# ESP8266_Led_Driver.net
KiCad netlist of a schematic drawn in EAGLE
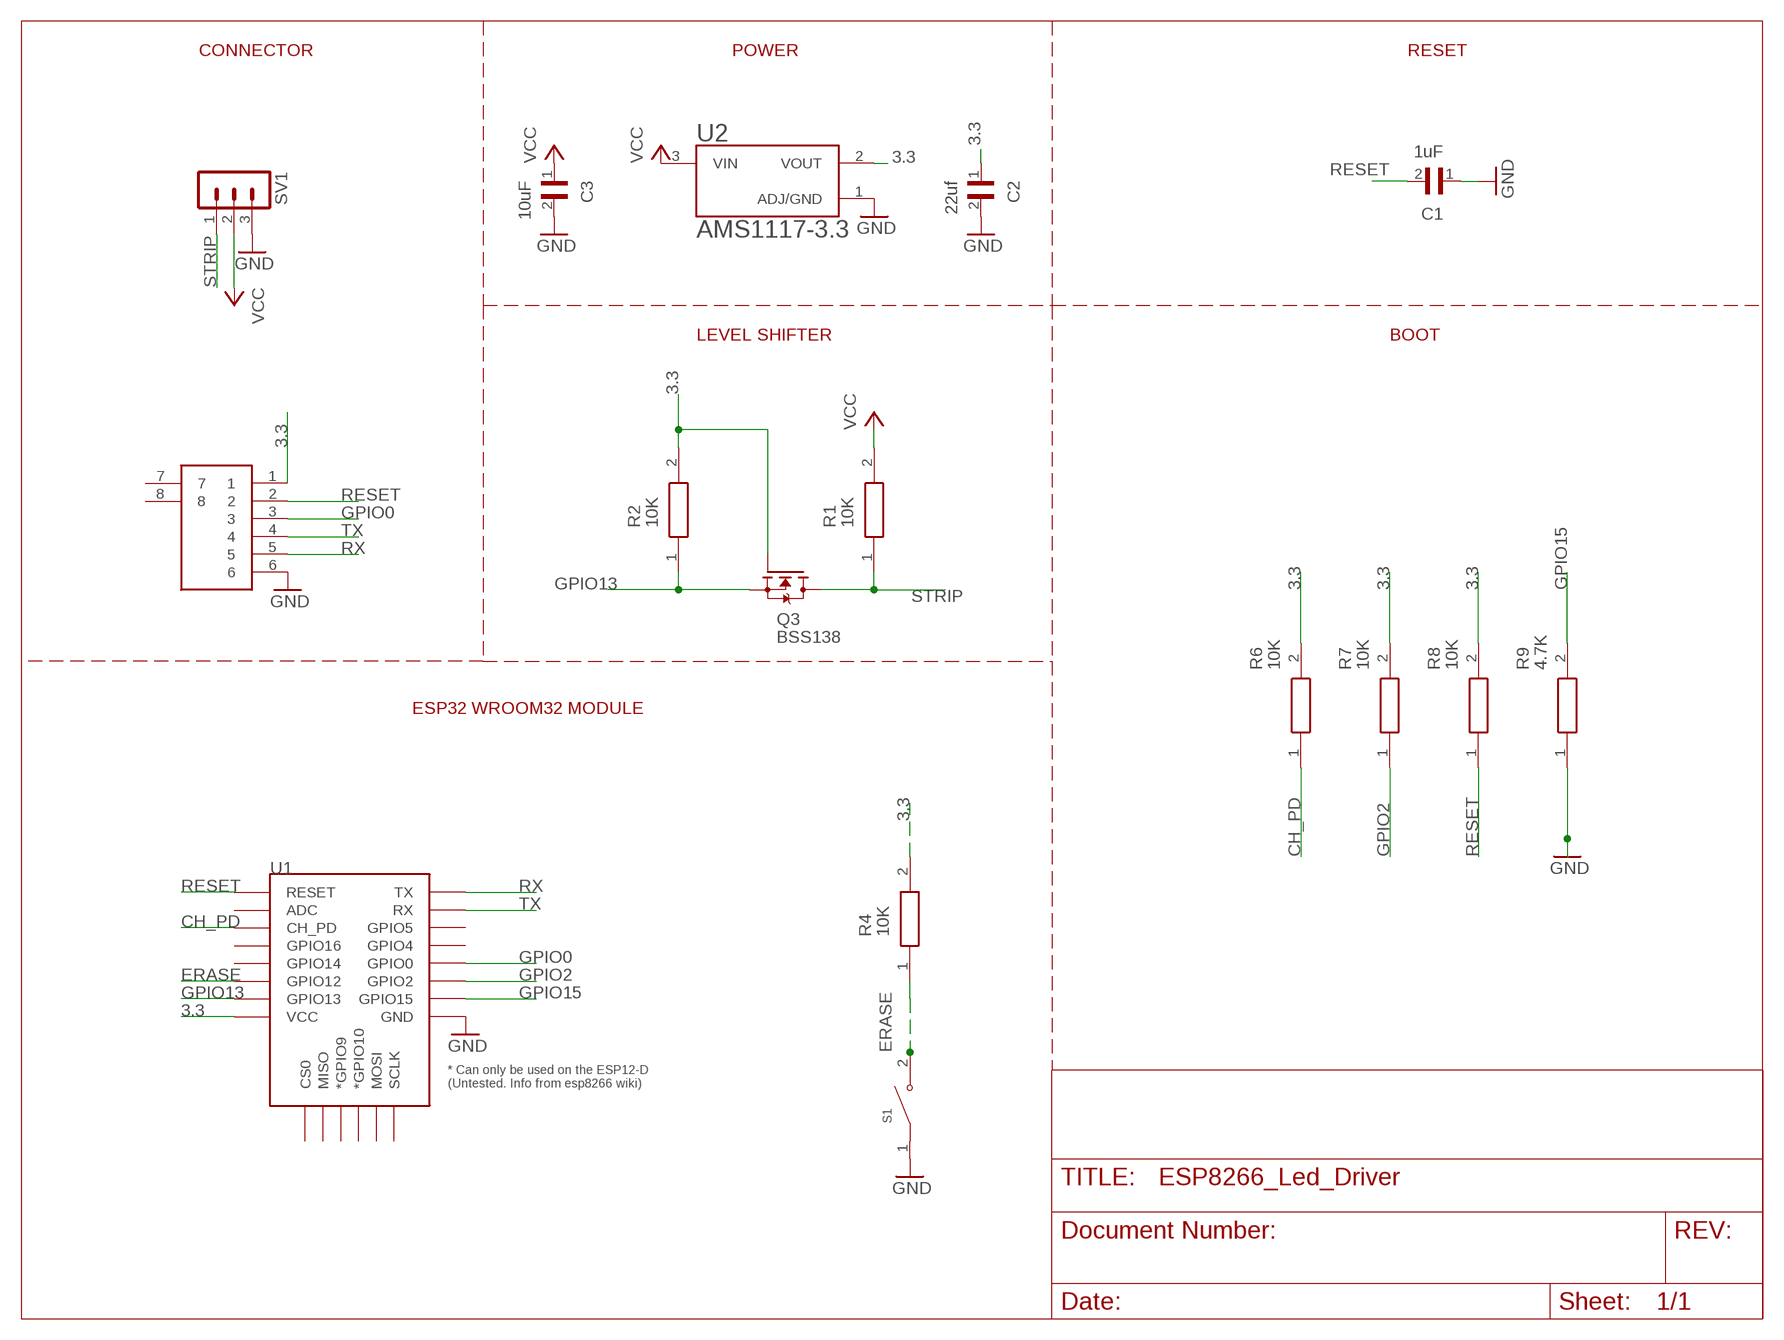
[diagram p0: schematic, sheet 1]

(export (version "E")
  (design (tool "Eeschema 10.0.6"))
  (components
    (comp (ref "C1")
      (value "1uF")
      (footprint "eagle-import:CAPC2012X94N")
      (fields (field (name "MF") "AVX") (field (name "MP") "0805YC103J4T2A"))
      (libsource (lib "eagle-import") (part "0805YC103J4T2A"))
    )
    (comp (ref "C2")
      (value "22uf")
      (footprint "eagle-import:CAPC2012X94N")
      (fields (field (name "MF") "AVX") (field (name "MP") "0805YC103J4T2A"))
      (libsource (lib "eagle-import") (part "0805YC103J4T2A"))
    )
    (comp (ref "C3")
      (value "10uF")
      (footprint "eagle-import:CAPC2012X94N")
      (fields (field (name "MF") "AVX") (field (name "MP") "0805YC103J4T2A"))
      (libsource (lib "eagle-import") (part "0805YC103J4T2A"))
    )
    (comp (ref "J1")
      (value "52852-0670")
      (footprint "eagle-import:528520670")
      (fields (field (name "MOUSER_PART_NUMBER") "538-52852-0670"))
      (libsource (lib "eagle-import") (part "52852-0670"))
    )
    (comp (ref "Q3")
      (value "BSS138")
      (footprint "eagle-import:SOT95P240X111-3N")
      (fields (field (name "MF") "ON Semiconductor"))
      (libsource (lib "eagle-import") (part "BSS138"))
    )
    (comp (ref "R1")
      (value "10K")
      (footprint "eagle-import:RESC1608X55N")
      (fields
        (field (name "MANUFACTURER_PART_NUMBER") "TNPW060330K0BXEA")
        (field (name "MOUSER_PART_NUMBER") "71-TNPW060330K0BXEA")
      )
      (libsource (lib "eagle-import") (part "TNPW060330K0BXEA"))
    )
    (comp (ref "R2")
      (value "10K")
      (footprint "eagle-import:RESC1608X55N")
      (fields
        (field (name "MANUFACTURER_PART_NUMBER") "TNPW060330K0BXEA")
        (field (name "MOUSER_PART_NUMBER") "71-TNPW060330K0BXEA")
      )
      (libsource (lib "eagle-import") (part "TNPW060330K0BXEA"))
    )
    (comp (ref "R4")
      (value "10K")
      (footprint "eagle-import:RESC1608X55N")
      (fields
        (field (name "MANUFACTURER_PART_NUMBER") "TNPW060330K0BXEA")
        (field (name "MOUSER_PART_NUMBER") "71-TNPW060330K0BXEA")
      )
      (libsource (lib "eagle-import") (part "TNPW060330K0BXEA"))
    )
    (comp (ref "R6")
      (value "10K")
      (footprint "eagle-import:RESC1608X55N")
      (fields
        (field (name "MANUFACTURER_PART_NUMBER") "TNPW060330K0BXEA")
        (field (name "MOUSER_PART_NUMBER") "71-TNPW060330K0BXEA")
      )
      (libsource (lib "eagle-import") (part "TNPW060330K0BXEA"))
    )
    (comp (ref "R7")
      (value "10K")
      (footprint "eagle-import:RESC1608X55N")
      (fields
        (field (name "MANUFACTURER_PART_NUMBER") "TNPW060330K0BXEA")
        (field (name "MOUSER_PART_NUMBER") "71-TNPW060330K0BXEA")
      )
      (libsource (lib "eagle-import") (part "TNPW060330K0BXEA"))
    )
    (comp (ref "R8")
      (value "10K")
      (footprint "eagle-import:RESC1608X55N")
      (fields
        (field (name "MANUFACTURER_PART_NUMBER") "TNPW060330K0BXEA")
        (field (name "MOUSER_PART_NUMBER") "71-TNPW060330K0BXEA")
      )
      (libsource (lib "eagle-import") (part "TNPW060330K0BXEA"))
    )
    (comp (ref "R9")
      (value "4.7K")
      (footprint "eagle-import:RESC1608X55N")
      (fields
        (field (name "MANUFACTURER_PART_NUMBER") "TNPW060330K0BXEA")
        (field (name "MOUSER_PART_NUMBER") "71-TNPW060330K0BXEA")
      )
      (libsource (lib "eagle-import") (part "TNPW060330K0BXEA"))
    )
    (comp (ref "S1")
      (value "PTS636_SM43J_SMTR_LFS")
      (footprint "eagle-import:SW_PTS636_SM43J_SMTR_LFS")
      (fields (field (name "MF") "C&K") (field (name "MP") "PTS636 SM43J SMTR LFS"))
      (libsource (lib "eagle-import") (part "PTS636_SM43J_SMTR_LFS"))
    )
    (comp (ref "SV1")
      (value "MA03-1")
      (footprint "eagle-import:MA03-1")
      (libsource (lib "eagle-import") (part "MA03-1"))
    )
    (comp (ref "U1")
      (value "ESP12ESMD")
      (footprint "eagle-import:ESP12E-SMD")
      (libsource (lib "eagle-import") (part "ESP12ESMD"))
    )
    (comp (ref "U2")
      (value "AMS1117-3.3")
      (footprint "eagle-import:SOT229P700X180-4N")
      (fields (field (name "MF") "Advanced Monolithic Systems"))
      (libsource (lib "eagle-import") (part "AMS1117-3.3"))
    )
  )
  (nets
    (net (code "1") (name "/3.3") (class "Default")
      (node (ref "C2") (pin "1") (pinfunction "1_1") (pintype "passive"))
      (node (ref "J1") (pin "1") (pinfunction "1_1") (pintype "bidirectional"))
      (node (ref "Q3") (pin "1") (pinfunction "G_1") (pintype "passive"))
      (node (ref "R2") (pin "2") (pinfunction "2_2") (pintype "bidirectional"))
      (node (ref "R4") (pin "2") (pinfunction "2_2") (pintype "bidirectional"))
      (node (ref "R6") (pin "2") (pinfunction "2_2") (pintype "bidirectional"))
      (node (ref "R7") (pin "2") (pinfunction "2_2") (pintype "bidirectional"))
      (node (ref "R8") (pin "2") (pinfunction "2_2") (pintype "bidirectional"))
      (node (ref "U1") (pin "VCC") (pinfunction "VCC_VCC") (pintype "bidirectional"))
      (node (ref "U2") (pin "2") (pinfunction "VOUT_2") (pintype "output"))
    )
    (net (code "2") (name "/CH_PD") (class "Default")
      (node (ref "R6") (pin "1") (pinfunction "1_1") (pintype "bidirectional"))
      (node (ref "U1") (pin "CH_PD") (pinfunction "CH_PD_CH_PD") (pintype "bidirectional"))
    )
    (net (code "3") (name "/ERASE") (class "Default")
      (node (ref "R4") (pin "1") (pinfunction "1_1") (pintype "bidirectional"))
      (node (ref "S1") (pin "2") (pinfunction "NO_2") (pintype "passive"))
      (node (ref "U1") (pin "GPIO12") (pinfunction "GPIO12_GPIO12") (pintype "bidirectional"))
    )
    (net (code "4") (name "/GPIO0") (class "Default")
      (node (ref "J1") (pin "3") (pinfunction "3_3") (pintype "bidirectional"))
      (node (ref "U1") (pin "GPIO0") (pinfunction "GPIO0_GPIO0") (pintype "bidirectional"))
    )
    (net (code "5") (name "/GPIO2") (class "Default")
      (node (ref "R7") (pin "1") (pinfunction "1_1") (pintype "bidirectional"))
      (node (ref "U1") (pin "GPIO2") (pinfunction "GPIO2_GPIO2") (pintype "bidirectional"))
    )
    (net (code "6") (name "/GPIO13") (class "Default")
      (node (ref "Q3") (pin "2") (pinfunction "S_2") (pintype "passive"))
      (node (ref "R2") (pin "1") (pinfunction "1_1") (pintype "bidirectional"))
      (node (ref "U1") (pin "GPIO13") (pinfunction "GPIO13_GPIO13") (pintype "bidirectional"))
    )
    (net (code "7") (name "/GPIO15") (class "Default")
      (node (ref "R9") (pin "2") (pinfunction "2_2") (pintype "bidirectional"))
      (node (ref "U1") (pin "GPIO15") (pinfunction "GPIO15_GPIO15") (pintype "bidirectional"))
    )
    (net (code "8") (name "/RESET") (class "Default")
      (node (ref "C1") (pin "2") (pinfunction "2_2") (pintype "passive"))
      (node (ref "J1") (pin "2") (pinfunction "2_2") (pintype "bidirectional"))
      (node (ref "R8") (pin "1") (pinfunction "1_1") (pintype "bidirectional"))
      (node (ref "U1") (pin "RESET") (pinfunction "RESET_RESET") (pintype "bidirectional"))
    )
    (net (code "9") (name "/RX") (class "Default")
      (node (ref "J1") (pin "5") (pinfunction "5_5") (pintype "bidirectional"))
      (node (ref "U1") (pin "TXD0") (pinfunction "TX_TXD0") (pintype "bidirectional"))
    )
    (net (code "10") (name "/STRIP") (class "Default")
      (node (ref "Q3") (pin "3") (pinfunction "D_3") (pintype "passive"))
      (node (ref "R1") (pin "1") (pinfunction "1_1") (pintype "bidirectional"))
      (node (ref "SV1") (pin "1") (pinfunction "1_1") (pintype "passive"))
    )
    (net (code "11") (name "/TX") (class "Default")
      (node (ref "J1") (pin "4") (pinfunction "4_4") (pintype "bidirectional"))
      (node (ref "U1") (pin "RXD0") (pinfunction "RX_RXD0") (pintype "bidirectional"))
    )
    (net (code "12") (name "GND") (class "Default")
      (node (ref "C1") (pin "1") (pinfunction "1_1") (pintype "passive"))
      (node (ref "C2") (pin "2") (pinfunction "2_2") (pintype "passive"))
      (node (ref "C3") (pin "2") (pinfunction "2_2") (pintype "passive"))
      (node (ref "J1") (pin "6") (pinfunction "6_6") (pintype "bidirectional"))
      (node (ref "R9") (pin "1") (pinfunction "1_1") (pintype "bidirectional"))
      (node (ref "S1") (pin "1") (pinfunction "COM_1") (pintype "passive"))
      (node (ref "SV1") (pin "3") (pinfunction "3_3") (pintype "passive"))
      (node (ref "U1") (pin "GND") (pinfunction "GND_GND") (pintype "bidirectional"))
      (node (ref "U2") (pin "1") (pinfunction "ADJ/GND_1") (pintype "power_in"))
    )
    (net (code "13") (name "VCC") (class "Default")
      (node (ref "C3") (pin "1") (pinfunction "1_1") (pintype "passive"))
      (node (ref "R1") (pin "2") (pinfunction "2_2") (pintype "bidirectional"))
      (node (ref "SV1") (pin "2") (pinfunction "2_2") (pintype "passive"))
      (node (ref "U2") (pin "3") (pinfunction "VIN_3") (pintype "input"))
    )
    (net (code "14") (name "unconnected-(J1-Pad7)") (class "Default")
      (node (ref "J1") (pin "7") (pinfunction "7_7") (pintype "bidirectional"))
    )
    (net (code "15") (name "unconnected-(J1-Pad8)") (class "Default")
      (node (ref "J1") (pin "8") (pinfunction "8_8") (pintype "bidirectional"))
    )
    (net (code "16") (name "unconnected-(U1-*GPIO9-PadGPIO9)") (class "Default")
      (node (ref "U1") (pin "GPIO9") (pinfunction "*GPIO9_GPIO9") (pintype "bidirectional"))
    )
    (net (code "17") (name "unconnected-(U1-*GPIO10-PadGPIO10)") (class "Default")
      (node (ref "U1") (pin "GPIO10") (pinfunction "*GPIO10_GPIO10") (pintype "bidirectional"))
    )
    (net (code "18") (name "unconnected-(U1-PadADC)") (class "Default")
      (node (ref "U1") (pin "ADC") (pinfunction "ADC_ADC") (pintype "bidirectional"))
    )
    (net (code "19") (name "unconnected-(U1-PadCS0)") (class "Default")
      (node (ref "U1") (pin "CS0") (pinfunction "CS0_CS0") (pintype "bidirectional"))
    )
    (net (code "20") (name "unconnected-(U1-PadGPIO4)") (class "Default")
      (node (ref "U1") (pin "GPIO4") (pinfunction "GPIO4_GPIO4") (pintype "bidirectional"))
    )
    (net (code "21") (name "unconnected-(U1-PadGPIO5)") (class "Default")
      (node (ref "U1") (pin "GPIO5") (pinfunction "GPIO5_GPIO5") (pintype "bidirectional"))
    )
    (net (code "22") (name "unconnected-(U1-PadGPIO14)") (class "Default")
      (node (ref "U1") (pin "GPIO14") (pinfunction "GPIO14_GPIO14") (pintype "bidirectional"))
    )
    (net (code "23") (name "unconnected-(U1-PadGPIO16)") (class "Default")
      (node (ref "U1") (pin "GPIO16") (pinfunction "GPIO16_GPIO16") (pintype "bidirectional"))
    )
    (net (code "24") (name "unconnected-(U1-PadMISO)") (class "Default")
      (node (ref "U1") (pin "MISO") (pinfunction "MISO_MISO") (pintype "bidirectional"))
    )
    (net (code "25") (name "unconnected-(U1-PadMOSI)") (class "Default")
      (node (ref "U1") (pin "MOSI") (pinfunction "MOSI_MOSI") (pintype "bidirectional"))
    )
    (net (code "26") (name "unconnected-(U1-PadSCLK)") (class "Default")
      (node (ref "U1") (pin "SCLK") (pinfunction "SCLK_SCLK") (pintype "bidirectional"))
    )
  )
)
